# Amplifier-TPA2016D2.net
KiCad netlist of a schematic drawn in Altium Designer
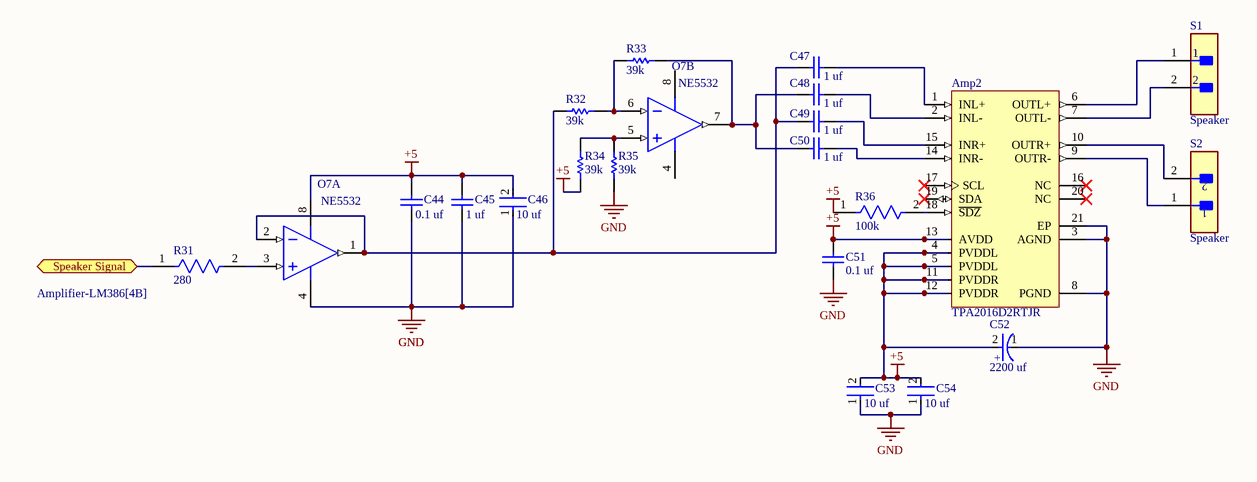
[diagram p0: Amplifier-TPA2016D2.SchDoc]

(export (version "E")
  (design (tool "Eeschema 10.0.6"))
  (components
    (comp (ref "Amp2")
      (value "TPA2016D2RTJR")
      (footprint "RTJ0020D_V")
      (fields (field (name "MANUFACTURER") "Texas Instruments"))
      (libsource (lib "Altium Content Vault") (part "TI-TPA2016D2RTJ20-2700X2700TP"))
    )
    (comp (ref "C44")
      (value "0.1 uf")
      (footprint "CAPC2013X135X45ML10T25")
      (description "Chip Capacitor, 0.1 uF, +/- 10%, 50 V, -55 to 125 degC, 0805 (2012 Metric), RoHS, Tape and Reel")
      (fields (field (name "VOLTAGE") "50V") (field (name "TOLERANCE") "10%"))
      (libsource (lib "Altium Content Vault") (part "CAP-NP-2"))
    )
    (comp (ref "C45")
      (value "1 uf")
      (footprint "CAPC2013X145X50LL20T25")
      (fields (field (name "MANUFACTURER") "Kemet") (field (name "PART NUMBER") "C0805C105K4PACTU"))
      (libsource (lib "Altium Content Vault") (part "CAP"))
    )
    (comp (ref "C46")
      (value "10 uf")
      (footprint "FP-C0805C-DG-MFG")
      (description "CAP CER 10UF 10V X5R 0805")
      (fields (field (name "TOLERANCE") "10%") (field (name "MANUFACTURER PART NUMBER") "C0805C106K8PACTU"))
      (libsource (lib "Altium Content Vault") (part "11868f565c42a9108669ba33697ecf6"))
    )
    (comp (ref "C47")
      (value "1 uf")
      (footprint "CAPC2013X135X45ML10T25")
      (description "Chip Capacitor, 0.1 uF, +/- 10%, 50 V, -55 to 125 degC, 0805 (2012 Metric), RoHS, Tape and Reel")
      (fields (field (name "VOLTAGE") "50V") (field (name "TOLERANCE") "10%"))
      (libsource (lib "Altium Content Vault") (part "CAP-NP-2"))
    )
    (comp (ref "C48")
      (value "1 uf")
      (footprint "CAPC2013X135X45ML10T25")
      (description "Chip Capacitor, 0.1 uF, +/- 10%, 50 V, -55 to 125 degC, 0805 (2012 Metric), RoHS, Tape and Reel")
      (fields (field (name "VOLTAGE") "50V") (field (name "TOLERANCE") "10%"))
      (libsource (lib "Altium Content Vault") (part "CAP-NP-2"))
    )
    (comp (ref "C49")
      (value "1 uf")
      (footprint "CAPC2013X135X45ML10T25")
      (description "Chip Capacitor, 0.1 uF, +/- 10%, 50 V, -55 to 125 degC, 0805 (2012 Metric), RoHS, Tape and Reel")
      (fields (field (name "VOLTAGE") "50V") (field (name "TOLERANCE") "10%"))
      (libsource (lib "Altium Content Vault") (part "CAP-NP-2"))
    )
    (comp (ref "C50")
      (value "1 uf")
      (footprint "CAPC2013X135X45ML10T25")
      (description "Chip Capacitor, 0.1 uF, +/- 10%, 50 V, -55 to 125 degC, 0805 (2012 Metric), RoHS, Tape and Reel")
      (fields (field (name "VOLTAGE") "50V") (field (name "TOLERANCE") "10%"))
      (libsource (lib "Altium Content Vault") (part "CAP-NP-2"))
    )
    (comp (ref "C51")
      (value "0.1 uf")
      (footprint "CAPC2013X135X45ML10T25")
      (description "Chip Capacitor, 0.1 uF, +/- 10%, 50 V, -55 to 125 degC, 0805 (2012 Metric), RoHS, Tape and Reel")
      (fields (field (name "VOLTAGE") "50V") (field (name "TOLERANCE") "10%"))
      (libsource (lib "Altium Content Vault") (part "CAP-NP-2"))
    )
    (comp (ref "C52")
      (value "2200 uf")
      (footprint "FP-RAD-TH-D_10_0_5-L_16_1-MFG")
      (description "Aluminum Electrolytic Capacitors (Radial Lead Type) AEC-Q200 Qualified 470uF ±20% 25V")
      (fields (field (name "TOLERANCE") "20%") (field (name "VOLTAGE") "25V"))
      (libsource (lib "Altium Content Vault") (part "a00bbbee19879c290e62620ae7e47b1"))
    )
    (comp (ref "C53")
      (value "10 uf")
      (footprint "FP-C0805C-DG-MFG")
      (description "CAP CER 10UF 10V X5R 0805")
      (fields (field (name "TOLERANCE") "10%") (field (name "MANUFACTURER PART NUMBER") "C0805C106K8PACTU"))
      (libsource (lib "Altium Content Vault") (part "11868f565c42a9108669ba33697ecf6"))
    )
    (comp (ref "C54")
      (value "10 uf")
      (footprint "FP-C0805C-DG-MFG")
      (description "CAP CER 10UF 10V X5R 0805")
      (fields (field (name "TOLERANCE") "10%") (field (name "MANUFACTURER PART NUMBER") "C0805C106K8PACTU"))
      (libsource (lib "Altium Content Vault") (part "11868f565c42a9108669ba33697ecf6"))
    )
    (comp (ref "O7")
      (value "NE5532")
      (footprint "ONSC-SOIC-8-751-07_V")
      (fields (field (name "MANUFACTURER") "On Semiconductor") (field (name "PARTNUMBER") "NE5532AD8R2G"))
      (libsource (lib "Altium Content Vault") (part "ONSC-NE5532-SOIC-8-751-07"))
    )
    (comp (ref "R31")
      (value "280")
      (footprint "FP-CRCW0805-e3-MFG")
      (description "RES Thick Film, 280Ω, 1%, 0.125W, 100ppm/°C, 0805")
      (fields (field (name "TOLERANCE") "1%"))
      (libsource (lib "Altium Content Vault") (part "1029c3af85768c4190bb7ad29bc67b5"))
    )
    (comp (ref "R32")
      (value "39k")
      (footprint "RESC2013X70X40NL20T20")
      (fields (field (name "PART NUMBER") "ERJ-6GEYJ393V") (field (name "MANUFACTURER") "Panasonic"))
      (libsource (lib "Altium Content Vault") (part "RES"))
    )
    (comp (ref "R33")
      (value "39k")
      (footprint "RESC2013X70X40NL20T20")
      (fields (field (name "PART NUMBER") "ERJ-6GEYJ393V") (field (name "MANUFACTURER") "Panasonic"))
      (libsource (lib "Altium Content Vault") (part "RES"))
    )
    (comp (ref "R34")
      (value "39k")
      (footprint "RESC2013X70X40NL20T20")
      (fields (field (name "PART NUMBER") "ERJ-6GEYJ393V") (field (name "MANUFACTURER") "Panasonic"))
      (libsource (lib "Altium Content Vault") (part "RES"))
    )
    (comp (ref "R35")
      (value "39k")
      (footprint "RESC2013X70X40NL20T20")
      (fields (field (name "PART NUMBER") "ERJ-6GEYJ393V") (field (name "MANUFACTURER") "Panasonic"))
      (libsource (lib "Altium Content Vault") (part "RES"))
    )
    (comp (ref "R36")
      (value "100k")
      (footprint "FP-RC0805-0_6-IPC_C")
      (description "RES 100K OHM 1% 1/8W 0805")
      (fields (field (name "TOLERANCE") "1%"))
      (libsource (lib "Altium Content Vault") (part "1029c3af85768c4190bb7ad29bc67b5"))
    )
    (comp (ref "S1")
      (value "Speaker")
      (footprint "FP-B2B-XH-A_LF_SN-MFG")
      (description "CONN HEADER VERT 2POS 2.5MM")
      (libsource (lib "") (part "3bc925449376181038e59eaffc5286c_1"))
    )
    (comp (ref "S2")
      (value "Speaker")
      (footprint "FP-B2B-XH-A_LF_SN-MFG")
      (description "CONN HEADER VERT 2POS 2.5MM")
      (libsource (lib "Altium Content Vault") (part "3bc925449376181038e59eaffc5286c"))
    )
  )
  (nets
    (net (code "1") (name "+5") (class "Default")
      (node (ref "Amp2") (pin "11") (pinfunction "PVDDR_11") (pintype "power_in"))
      (node (ref "Amp2") (pin "12") (pinfunction "PVDDR_12") (pintype "power_in"))
      (node (ref "Amp2") (pin "13") (pinfunction "AVDD_13") (pintype "power_in"))
      (node (ref "Amp2") (pin "4") (pinfunction "PVDDL_4") (pintype "power_in"))
      (node (ref "Amp2") (pin "5") (pinfunction "PVDDL_5") (pintype "power_in"))
      (node (ref "C44") (pin "2") (pinfunction "2_2") (pintype "passive"))
      (node (ref "C45") (pin "1") (pinfunction "1_1") (pintype "passive"))
      (node (ref "C46") (pin "2") (pinfunction "2_2") (pintype "passive"))
      (node (ref "C51") (pin "2") (pinfunction "2_2") (pintype "passive"))
      (node (ref "C52") (pin "2") (pinfunction "A_2") (pintype "passive"))
      (node (ref "C53") (pin "2") (pinfunction "2_2") (pintype "passive"))
      (node (ref "C54") (pin "2") (pinfunction "2_2") (pintype "passive"))
      (node (ref "O7") (pin "8") (pinfunction "V+_8") (pintype "power_in"))
      (node (ref "R34") (pin "1") (pinfunction "1_1") (pintype "passive"))
      (node (ref "R36") (pin "1") (pinfunction "1_1") (pintype "passive"))
    )
    (net (code "2") (name "/Speaker Signal") (class "Default")
      (node (ref "R31") (pin "1") (pinfunction "1_1") (pintype "passive"))
    )
    (net (code "3") (name "GND") (class "Default")
      (node (ref "Amp2") (pin "21") (pinfunction "EP_21") (pintype "passive"))
      (node (ref "Amp2") (pin "3") (pinfunction "AGND_3") (pintype "power_in"))
      (node (ref "Amp2") (pin "8") (pinfunction "PGND_8") (pintype "power_in"))
      (node (ref "C44") (pin "1") (pinfunction "1_1") (pintype "passive"))
      (node (ref "C45") (pin "2") (pinfunction "2_2") (pintype "passive"))
      (node (ref "C46") (pin "1") (pinfunction "1_1") (pintype "passive"))
      (node (ref "C51") (pin "1") (pinfunction "1_1") (pintype "passive"))
      (node (ref "C52") (pin "1") (pinfunction "C_1") (pintype "passive"))
      (node (ref "C53") (pin "1") (pinfunction "1_1") (pintype "passive"))
      (node (ref "C54") (pin "1") (pinfunction "1_1") (pintype "passive"))
      (node (ref "O7") (pin "4") (pinfunction "V-_4") (pintype "power_in"))
      (node (ref "R35") (pin "1") (pinfunction "1_1") (pintype "passive"))
    )
    (net (code "4") (name "Net-(Amp2-INL+)") (class "Default")
      (node (ref "Amp2") (pin "1") (pinfunction "INL+_1") (pintype "input"))
      (node (ref "C47") (pin "2") (pinfunction "2_2") (pintype "passive"))
    )
    (net (code "5") (name "Net-(Amp2-INL-)") (class "Default")
      (node (ref "Amp2") (pin "2") (pinfunction "INL-_2") (pintype "input"))
      (node (ref "C48") (pin "2") (pinfunction "2_2") (pintype "passive"))
    )
    (net (code "6") (name "Net-(Amp2-INR+)") (class "Default")
      (node (ref "Amp2") (pin "15") (pinfunction "INR+_15") (pintype "input"))
      (node (ref "C49") (pin "2") (pinfunction "2_2") (pintype "passive"))
    )
    (net (code "7") (name "Net-(Amp2-INR-)") (class "Default")
      (node (ref "Amp2") (pin "14") (pinfunction "INR-_14") (pintype "input"))
      (node (ref "C50") (pin "2") (pinfunction "2_2") (pintype "passive"))
    )
    (net (code "8") (name "Net-(Amp2-OUTL+)") (class "Default")
      (node (ref "Amp2") (pin "6") (pinfunction "OUTL+_6") (pintype "output"))
      (node (ref "S1") (pin "1") (pinfunction "1_1") (pintype "passive"))
    )
    (net (code "9") (name "Net-(Amp2-OUTL-)") (class "Default")
      (node (ref "Amp2") (pin "7") (pinfunction "OUTL-_7") (pintype "output"))
      (node (ref "S1") (pin "2") (pinfunction "2_2") (pintype "passive"))
    )
    (net (code "10") (name "Net-(Amp2-OUTR+)") (class "Default")
      (node (ref "Amp2") (pin "10") (pinfunction "OUTR+_10") (pintype "output"))
      (node (ref "S2") (pin "2") (pinfunction "2_2") (pintype "passive"))
    )
    (net (code "11") (name "Net-(Amp2-OUTR-)") (class "Default")
      (node (ref "Amp2") (pin "9") (pinfunction "OUTR-_9") (pintype "output"))
      (node (ref "S2") (pin "1") (pinfunction "1_1") (pintype "passive"))
    )
    (net (code "12") (name "Net-(Amp2-~{SDZ})") (class "Default")
      (node (ref "Amp2") (pin "18") (pinfunction "~{SDZ}_18") (pintype "input"))
      (node (ref "R36") (pin "2") (pinfunction "2_2") (pintype "passive"))
    )
    (net (code "13") (name "Net-(O7A-INA+)") (class "Default")
      (node (ref "O7") (pin "3") (pinfunction "INA+_3") (pintype "input"))
      (node (ref "R31") (pin "2") (pinfunction "2_2") (pintype "passive"))
    )
    (net (code "14") (name "Net-(O7A-INA-)") (class "Default")
      (node (ref "C47") (pin "1") (pinfunction "1_1") (pintype "passive"))
      (node (ref "C49") (pin "1") (pinfunction "1_1") (pintype "passive"))
      (node (ref "O7") (pin "1") (pinfunction "OUTA_1") (pintype "output"))
      (node (ref "O7") (pin "2") (pinfunction "INA-_2") (pintype "input"))
      (node (ref "R32") (pin "1") (pinfunction "1_1") (pintype "passive"))
    )
    (net (code "15") (name "Net-(O7B-INB+)") (class "Default")
      (node (ref "O7") (pin "5") (pinfunction "INB+_5") (pintype "input"))
      (node (ref "R34") (pin "2") (pinfunction "2_2") (pintype "passive"))
      (node (ref "R35") (pin "2") (pinfunction "2_2") (pintype "passive"))
    )
    (net (code "16") (name "Net-(O7B-INB-)") (class "Default")
      (node (ref "O7") (pin "6") (pinfunction "INB-_6") (pintype "input"))
      (node (ref "R32") (pin "2") (pinfunction "2_2") (pintype "passive"))
      (node (ref "R33") (pin "1") (pinfunction "1_1") (pintype "passive"))
    )
    (net (code "17") (name "Net-(O7B-OUTB)") (class "Default")
      (node (ref "C48") (pin "1") (pinfunction "1_1") (pintype "passive"))
      (node (ref "C50") (pin "1") (pinfunction "1_1") (pintype "passive"))
      (node (ref "O7") (pin "7") (pinfunction "OUTB_7") (pintype "output"))
      (node (ref "R33") (pin "2") (pinfunction "2_2") (pintype "passive"))
    )
    (net (code "18") (name "unconnected-(Amp2-NC-Pad16)") (class "Default")
      (node (ref "Amp2") (pin "16") (pinfunction "NC_16") (pintype "passive+no_connect"))
    )
    (net (code "19") (name "unconnected-(Amp2-NC-Pad20)") (class "Default")
      (node (ref "Amp2") (pin "20") (pinfunction "NC_20") (pintype "passive+no_connect"))
    )
    (net (code "20") (name "unconnected-(Amp2-SCL-Pad17)") (class "Default")
      (node (ref "Amp2") (pin "17") (pinfunction "SCL_17") (pintype "input+no_connect"))
    )
    (net (code "21") (name "unconnected-(Amp2-SDA-Pad19)") (class "Default")
      (node (ref "Amp2") (pin "19") (pinfunction "SDA_19") (pintype "bidirectional+no_connect"))
    )
    (net (code "22") (name "unconnected-(O7B-V+-Pad8)") (class "Default")
      (node (ref "O7") (pin "8") (pinfunction "V+_8") (pintype "power_in"))
    )
    (net (code "23") (name "unconnected-(O7B-V--Pad4)") (class "Default")
      (node (ref "O7") (pin "4") (pinfunction "V-_4") (pintype "power_in"))
    )
  )
)
